# Lightbox_schematic_29OCT.net
KiCad netlist of a schematic drawn in EAGLE
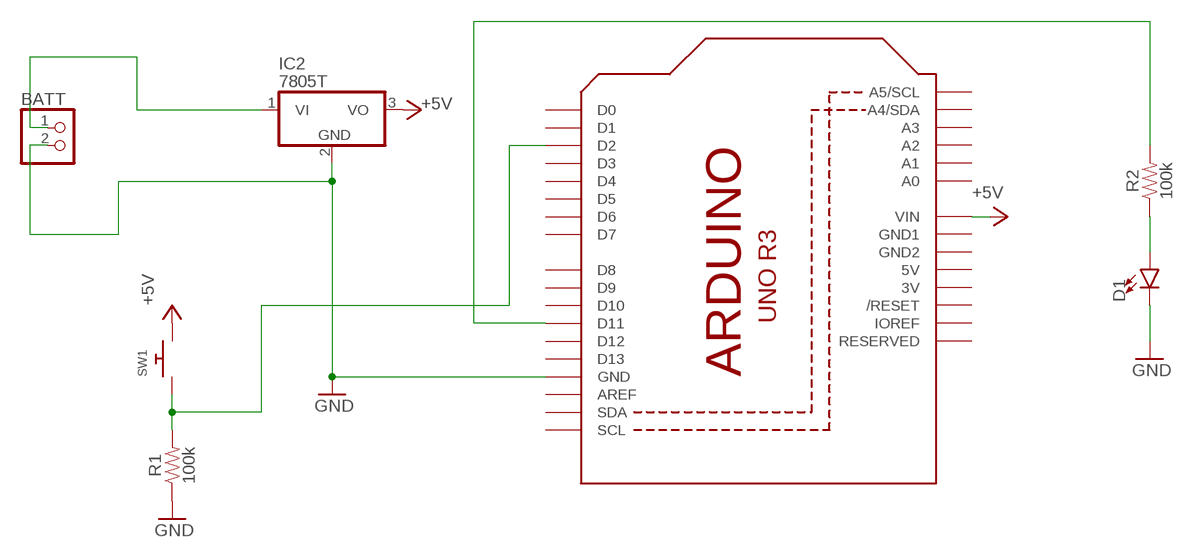
[diagram p0: schematic, sheet 1]

(export (version "E")
  (design (tool "Eeschema 10.0.6"))
  (components
    (comp (ref "BATT")
      (value "PINHD-1X2")
      (footprint "eagle-import:1X02")
      (libsource (lib "eagle-import") (part "PINHD-1X2"))
    )
    (comp (ref "D1")
      (value "LED3MM")
      (footprint "eagle-import:LED_3MM")
      (libsource (lib "eagle-import") (part "LED3MM"))
    )
    (comp (ref "IC2")
      (value "7805T")
      (footprint "eagle-import:TO220H")
      (libsource (lib "eagle-import") (part "78T05"))
    )
    (comp (ref "R1")
      (value "100k")
      (footprint "eagle-import:AXIAL-0.3")
      (libsource (lib "eagle-import") (part "100KOHM-HORIZ-1/4W-1%"))
    )
    (comp (ref "R2")
      (value "100k")
      (footprint "eagle-import:AXIAL-0.3")
      (libsource (lib "eagle-import") (part "100KOHM-HORIZ-1/4W-1%"))
    )
    (comp (ref "SW1")
      (value "SWITCH_PUSHBUTTONSOFTTOUCHSMD_SJ")
      (footprint "eagle-import:PUSHBUTTON_SMD_SJ")
      (libsource (lib "eagle-import") (part "SWITCH_PUSHBUTTONSOFTTOUCHSMD_SJ"))
    )
    (comp (ref "U1")
      (value "ARDUINOR3-DIMENSION")
      (footprint "eagle-import:ARDUINOR3")
      (libsource (lib "eagle-import") (part "ARDUINOR3-DIMENSION"))
    )
  )
  (nets
    (net (code "1") (name "+5V") (class "Default")
      (node (ref "IC2") (pin "3") (pinfunction "VO_3") (pintype "passive"))
      (node (ref "SW1") (pin "P$2") (pinfunction "P$2_P$2") (pintype "passive"))
      (node (ref "U1") (pin "VIN") (pinfunction "VIN_VIN") (pintype "power_in"))
    )
    (net (code "2") (name "/3V") (class "Default")
      (node (ref "U1") (pin "3V") (pinfunction "3V_3V") (pintype "power_in"))
    )
    (net (code "3") (name "/5V") (class "Default")
      (node (ref "U1") (pin "5V") (pinfunction "5V_5V") (pintype "power_in"))
    )
    (net (code "4") (name "/GND1") (class "Default")
      (node (ref "U1") (pin "GND1") (pinfunction "GND1_GND1") (pintype "power_in"))
    )
    (net (code "5") (name "/GND2") (class "Default")
      (node (ref "U1") (pin "GND2") (pinfunction "GND2_GND2") (pintype "power_in"))
    )
    (net (code "6") (name "GND") (class "Default")
      (node (ref "BATT") (pin "2") (pinfunction "2_2") (pintype "passive"))
      (node (ref "D1") (pin "K") (pinfunction "C_K") (pintype "passive"))
      (node (ref "IC2") (pin "2") (pinfunction "GND_2") (pintype "passive"))
      (node (ref "R1") (pin "P$1") (pinfunction "1_P$1") (pintype "passive"))
      (node (ref "U1") (pin "GND") (pinfunction "GND_GND") (pintype "power_in"))
    )
    (net (code "7") (name "Net-(IC2-VI)") (class "Default")
      (node (ref "BATT") (pin "1") (pinfunction "1_1") (pintype "passive"))
      (node (ref "IC2") (pin "1") (pinfunction "VI_1") (pintype "input"))
    )
    (net (code "8") (name "Net-(R1-2)") (class "Default")
      (node (ref "R1") (pin "P$2") (pinfunction "2_P$2") (pintype "passive"))
      (node (ref "SW1") (pin "P$1") (pinfunction "P$1_P$1") (pintype "passive"))
      (node (ref "U1") (pin "D2") (pinfunction "D2_D2") (pintype "bidirectional"))
    )
    (net (code "9") (name "Net-(R2-1)") (class "Default")
      (node (ref "D1") (pin "A") (pinfunction "A_A") (pintype "passive"))
      (node (ref "R2") (pin "P$1") (pinfunction "1_P$1") (pintype "passive"))
    )
    (net (code "10") (name "Net-(R2-2)") (class "Default")
      (node (ref "R2") (pin "P$2") (pinfunction "2_P$2") (pintype "passive"))
      (node (ref "U1") (pin "D11") (pinfunction "D11_D11") (pintype "bidirectional"))
    )
    (net (code "11") (name "unconnected-(U1-A4{slash}SDA-PadA4)") (class "Default")
      (node (ref "U1") (pin "A4") (pinfunction "A4/SDA_A4") (pintype "bidirectional"))
    )
    (net (code "12") (name "unconnected-(U1-A5{slash}SCL-PadA5)") (class "Default")
      (node (ref "U1") (pin "A5") (pinfunction "A5/SCL_A5") (pintype "bidirectional"))
    )
    (net (code "13") (name "unconnected-(U1-PadA0)") (class "Default")
      (node (ref "U1") (pin "A0") (pinfunction "A0_A0") (pintype "bidirectional"))
    )
    (net (code "14") (name "unconnected-(U1-PadA1)") (class "Default")
      (node (ref "U1") (pin "A1") (pinfunction "A1_A1") (pintype "bidirectional"))
    )
    (net (code "15") (name "unconnected-(U1-PadA2)") (class "Default")
      (node (ref "U1") (pin "A2") (pinfunction "A2_A2") (pintype "bidirectional"))
    )
    (net (code "16") (name "unconnected-(U1-PadA3)") (class "Default")
      (node (ref "U1") (pin "A3") (pinfunction "A3_A3") (pintype "bidirectional"))
    )
    (net (code "17") (name "unconnected-(U1-PadAREF)") (class "Default")
      (node (ref "U1") (pin "AREF") (pinfunction "AREF_AREF") (pintype "bidirectional"))
    )
    (net (code "18") (name "unconnected-(U1-PadD0)") (class "Default")
      (node (ref "U1") (pin "D0") (pinfunction "D0_D0") (pintype "bidirectional"))
    )
    (net (code "19") (name "unconnected-(U1-PadD1)") (class "Default")
      (node (ref "U1") (pin "D1") (pinfunction "D1_D1") (pintype "bidirectional"))
    )
    (net (code "20") (name "unconnected-(U1-PadD3)") (class "Default")
      (node (ref "U1") (pin "D3") (pinfunction "D3_D3") (pintype "bidirectional"))
    )
    (net (code "21") (name "unconnected-(U1-PadD4)") (class "Default")
      (node (ref "U1") (pin "D4") (pinfunction "D4_D4") (pintype "bidirectional"))
    )
    (net (code "22") (name "unconnected-(U1-PadD5)") (class "Default")
      (node (ref "U1") (pin "D5") (pinfunction "D5_D5") (pintype "bidirectional"))
    )
    (net (code "23") (name "unconnected-(U1-PadD6)") (class "Default")
      (node (ref "U1") (pin "D6") (pinfunction "D6_D6") (pintype "bidirectional"))
    )
    (net (code "24") (name "unconnected-(U1-PadD7)") (class "Default")
      (node (ref "U1") (pin "D7") (pinfunction "D7_D7") (pintype "bidirectional"))
    )
    (net (code "25") (name "unconnected-(U1-PadD8)") (class "Default")
      (node (ref "U1") (pin "D8") (pinfunction "D8_D8") (pintype "bidirectional"))
    )
    (net (code "26") (name "unconnected-(U1-PadD9)") (class "Default")
      (node (ref "U1") (pin "D9") (pinfunction "D9_D9") (pintype "bidirectional"))
    )
    (net (code "27") (name "unconnected-(U1-PadD10)") (class "Default")
      (node (ref "U1") (pin "D10") (pinfunction "D10_D10") (pintype "bidirectional"))
    )
    (net (code "28") (name "unconnected-(U1-PadD12)") (class "Default")
      (node (ref "U1") (pin "D12") (pinfunction "D12_D12") (pintype "bidirectional"))
    )
    (net (code "29") (name "unconnected-(U1-PadD13)") (class "Default")
      (node (ref "U1") (pin "D13") (pinfunction "D13_D13") (pintype "bidirectional"))
    )
    (net (code "30") (name "unconnected-(U1-PadIOREF)") (class "Default")
      (node (ref "U1") (pin "IOREF") (pinfunction "IOREF_IOREF") (pintype "output"))
    )
    (net (code "31") (name "unconnected-(U1-PadRESERVED)") (class "Default")
      (node (ref "U1") (pin "RESERVED") (pinfunction "RESERVED_RESERVED") (pintype "no_connect"))
    )
    (net (code "32") (name "unconnected-(U1-PadSCL)") (class "Default")
      (node (ref "U1") (pin "SCL") (pinfunction "SCL_SCL") (pintype "bidirectional"))
    )
    (net (code "33") (name "unconnected-(U1-PadSDA)") (class "Default")
      (node (ref "U1") (pin "SDA") (pinfunction "SDA_SDA") (pintype "bidirectional"))
    )
    (net (code "34") (name "unconnected-(U1-{slash}RESET-PadRESET)") (class "Default")
      (node (ref "U1") (pin "RESET") (pinfunction "/RESET_RESET") (pintype "bidirectional"))
    )
  )
)
